# magchess2.net
KiCad netlist of a schematic drawn in EAGLE
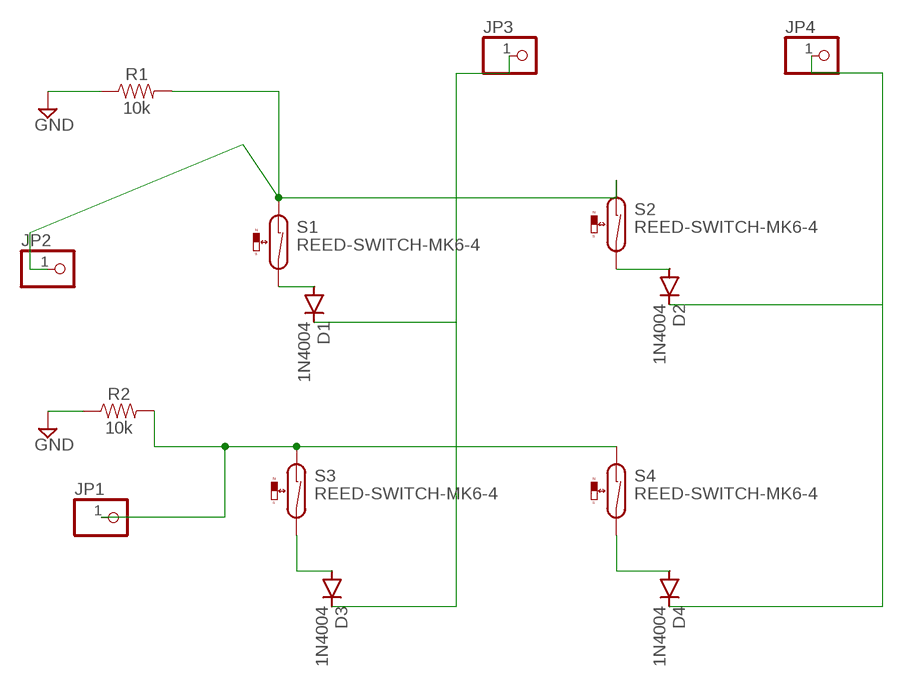
[diagram p0: schematic, sheet 1]

(export (version "E")
  (design (tool "Eeschema 10.0.6"))
  (components
    (comp (ref "D1")
      (value "1N4004")
      (footprint "eagle-import:DO41-10")
      (libsource (lib "eagle-import") (part "1N4004"))
    )
    (comp (ref "D2")
      (value "1N4004")
      (footprint "eagle-import:DO41-10")
      (libsource (lib "eagle-import") (part "1N4004"))
    )
    (comp (ref "D3")
      (value "1N4004")
      (footprint "eagle-import:DO41-10")
      (libsource (lib "eagle-import") (part "1N4004"))
    )
    (comp (ref "D4")
      (value "1N4004")
      (footprint "eagle-import:DO41-10")
      (libsource (lib "eagle-import") (part "1N4004"))
    )
    (comp (ref "JP1")
      (value "PINHD-1X1")
      (footprint "eagle-import:1X01")
      (libsource (lib "eagle-import") (part "PINHD-1X1"))
    )
    (comp (ref "JP2")
      (value "PINHD-1X1")
      (footprint "eagle-import:1X01")
      (libsource (lib "eagle-import") (part "PINHD-1X1"))
    )
    (comp (ref "JP3")
      (value "PINHD-1X1")
      (footprint "eagle-import:1X01")
      (libsource (lib "eagle-import") (part "PINHD-1X1"))
    )
    (comp (ref "JP4")
      (value "PINHD-1X1")
      (footprint "eagle-import:1X01")
      (libsource (lib "eagle-import") (part "PINHD-1X1"))
    )
    (comp (ref "R1")
      (value "10k")
      (footprint "eagle-import:AXIAL-0.3")
      (libsource (lib "eagle-import") (part "10KOHM-HORIZ-1/4W-5%"))
    )
    (comp (ref "R2")
      (value "10k")
      (footprint "eagle-import:AXIAL-0.3")
      (libsource (lib "eagle-import") (part "10KOHM-HORIZ-1/4W-5%"))
    )
    (comp (ref "S1")
      (value "REED-SWITCH-MK6-4")
      (footprint "eagle-import:MK6-4")
      (libsource (lib "eagle-import") (part "REED-SWITCH-MK6-4"))
    )
    (comp (ref "S2")
      (value "REED-SWITCH-MK6-4")
      (footprint "eagle-import:MK6-4")
      (libsource (lib "eagle-import") (part "REED-SWITCH-MK6-4"))
    )
    (comp (ref "S3")
      (value "REED-SWITCH-MK6-4")
      (footprint "eagle-import:MK6-4")
      (libsource (lib "eagle-import") (part "REED-SWITCH-MK6-4"))
    )
    (comp (ref "S4")
      (value "REED-SWITCH-MK6-4")
      (footprint "eagle-import:MK6-4")
      (libsource (lib "eagle-import") (part "REED-SWITCH-MK6-4"))
    )
  )
  (nets
    (net (code "1") (name "GND") (class "Default")
      (node (ref "R1") (pin "P$1") (pinfunction "1_P$1") (pintype "passive"))
      (node (ref "R2") (pin "P$1") (pinfunction "1_P$1") (pintype "passive"))
    )
    (net (code "2") (name "Net-(D1-PadA)") (class "Default")
      (node (ref "D1") (pin "A") (pinfunction "A_A") (pintype "passive"))
      (node (ref "S1") (pin "2") (pinfunction "2_2") (pintype "passive"))
    )
    (net (code "3") (name "Net-(D1-PadC)") (class "Default")
      (node (ref "D1") (pin "C") (pinfunction "C_C") (pintype "passive"))
      (node (ref "D3") (pin "C") (pinfunction "C_C") (pintype "passive"))
      (node (ref "JP3") (pin "1") (pinfunction "1_1") (pintype "passive"))
    )
    (net (code "4") (name "Net-(D2-PadA)") (class "Default")
      (node (ref "D2") (pin "A") (pinfunction "A_A") (pintype "passive"))
      (node (ref "S2") (pin "2") (pinfunction "2_2") (pintype "passive"))
    )
    (net (code "5") (name "Net-(D2-PadC)") (class "Default")
      (node (ref "D2") (pin "C") (pinfunction "C_C") (pintype "passive"))
      (node (ref "D4") (pin "C") (pinfunction "C_C") (pintype "passive"))
      (node (ref "JP4") (pin "1") (pinfunction "1_1") (pintype "passive"))
    )
    (net (code "6") (name "Net-(D3-PadA)") (class "Default")
      (node (ref "D3") (pin "A") (pinfunction "A_A") (pintype "passive"))
      (node (ref "S3") (pin "2") (pinfunction "2_2") (pintype "passive"))
    )
    (net (code "7") (name "Net-(D4-PadA)") (class "Default")
      (node (ref "D4") (pin "A") (pinfunction "A_A") (pintype "passive"))
      (node (ref "S4") (pin "2") (pinfunction "2_2") (pintype "passive"))
    )
    (net (code "8") (name "Net-(R1-2)") (class "Default")
      (node (ref "JP2") (pin "1") (pinfunction "1_1") (pintype "passive"))
      (node (ref "R1") (pin "P$2") (pinfunction "2_P$2") (pintype "passive"))
      (node (ref "S1") (pin "1") (pinfunction "1_1") (pintype "passive"))
      (node (ref "S2") (pin "1") (pinfunction "1_1") (pintype "passive"))
    )
    (net (code "9") (name "Net-(R2-2)") (class "Default")
      (node (ref "JP1") (pin "1") (pinfunction "1_1") (pintype "passive"))
      (node (ref "R2") (pin "P$2") (pinfunction "2_P$2") (pintype "passive"))
      (node (ref "S3") (pin "1") (pinfunction "1_1") (pintype "passive"))
      (node (ref "S4") (pin "1") (pinfunction "1_1") (pintype "passive"))
    )
  )
)
